# Driver.net
KiCad netlist of a schematic drawn in EAGLE
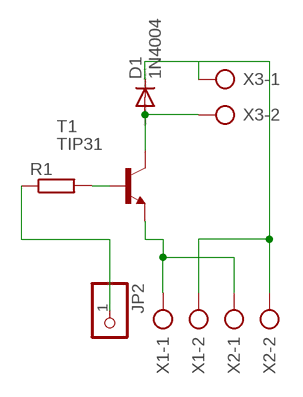
[diagram p0: schematic, sheet 1]

(export (version "E")
  (design (tool "Eeschema 10.0.6"))
  (components
    (comp (ref "D1")
      (value "1N4004")
      (footprint "eagle-import:DO41-10")
      (libsource (lib "eagle-import") (part "1N4004"))
    )
    (comp (ref "JP2")
      (value "PINHD-1X1")
      (footprint "eagle-import:1X01")
      (libsource (lib "eagle-import") (part "PINHD-1X1"))
    )
    (comp (ref "R1")
      (value "R-EU_0204/2V")
      (footprint "eagle-import:0204V")
      (libsource (lib "eagle-import") (part "R-EU_0204/2V"))
    )
    (comp (ref "T1")
      (value "TIP31")
      (footprint "eagle-import:TO220")
      (libsource (lib "eagle-import") (part "TIP31"))
    )
    (comp (ref "X1")
      (value "AK500/2-H")
      (footprint "eagle-import:AK500_2-H")
      (libsource (lib "eagle-import") (part "AK500/2-H"))
    )
    (comp (ref "X2")
      (value "AK500/2-H")
      (footprint "eagle-import:AK500_2-H")
      (libsource (lib "eagle-import") (part "AK500/2-H"))
    )
    (comp (ref "X3")
      (value "AK500/2-H")
      (footprint "eagle-import:AK500_2-H")
      (libsource (lib "eagle-import") (part "AK500/2-H"))
    )
  )
  (nets
    (net (code "1") (name "Net-(JP2-Pad1)") (class "Default")
      (node (ref "JP2") (pin "1") (pinfunction "1_1") (pintype "passive"))
      (node (ref "R1") (pin "1") (pinfunction "1_1") (pintype "passive"))
    )
    (net (code "2") (name "Net-(T1-B)") (class "Default")
      (node (ref "R1") (pin "2") (pinfunction "2_2") (pintype "passive"))
      (node (ref "T1") (pin "1") (pinfunction "B_1") (pintype "passive"))
    )
    (net (code "3") (name "Net-(T1-C)") (class "Default")
      (node (ref "D1") (pin "A") (pinfunction "A_A") (pintype "passive"))
      (node (ref "T1") (pin "2") (pinfunction "C_2") (pintype "passive"))
      (node (ref "X3") (pin "2") (pinfunction "KL_2") (pintype "passive"))
    )
    (net (code "4") (name "Net-(T1-E)") (class "Default")
      (node (ref "T1") (pin "3") (pinfunction "E_3") (pintype "passive"))
      (node (ref "X1") (pin "1") (pinfunction "KL_1") (pintype "passive"))
      (node (ref "X2") (pin "1") (pinfunction "KL_1") (pintype "passive"))
    )
    (net (code "5") (name "Net-(X1B-KL)") (class "Default")
      (node (ref "D1") (pin "C") (pinfunction "C_C") (pintype "passive"))
      (node (ref "X1") (pin "2") (pinfunction "KL_2") (pintype "passive"))
      (node (ref "X2") (pin "2") (pinfunction "KL_2") (pintype "passive"))
      (node (ref "X3") (pin "1") (pinfunction "KL_1") (pintype "passive"))
    )
  )
)
